# SmartEVSEv2.net
KiCad netlist of a schematic drawn in EAGLE
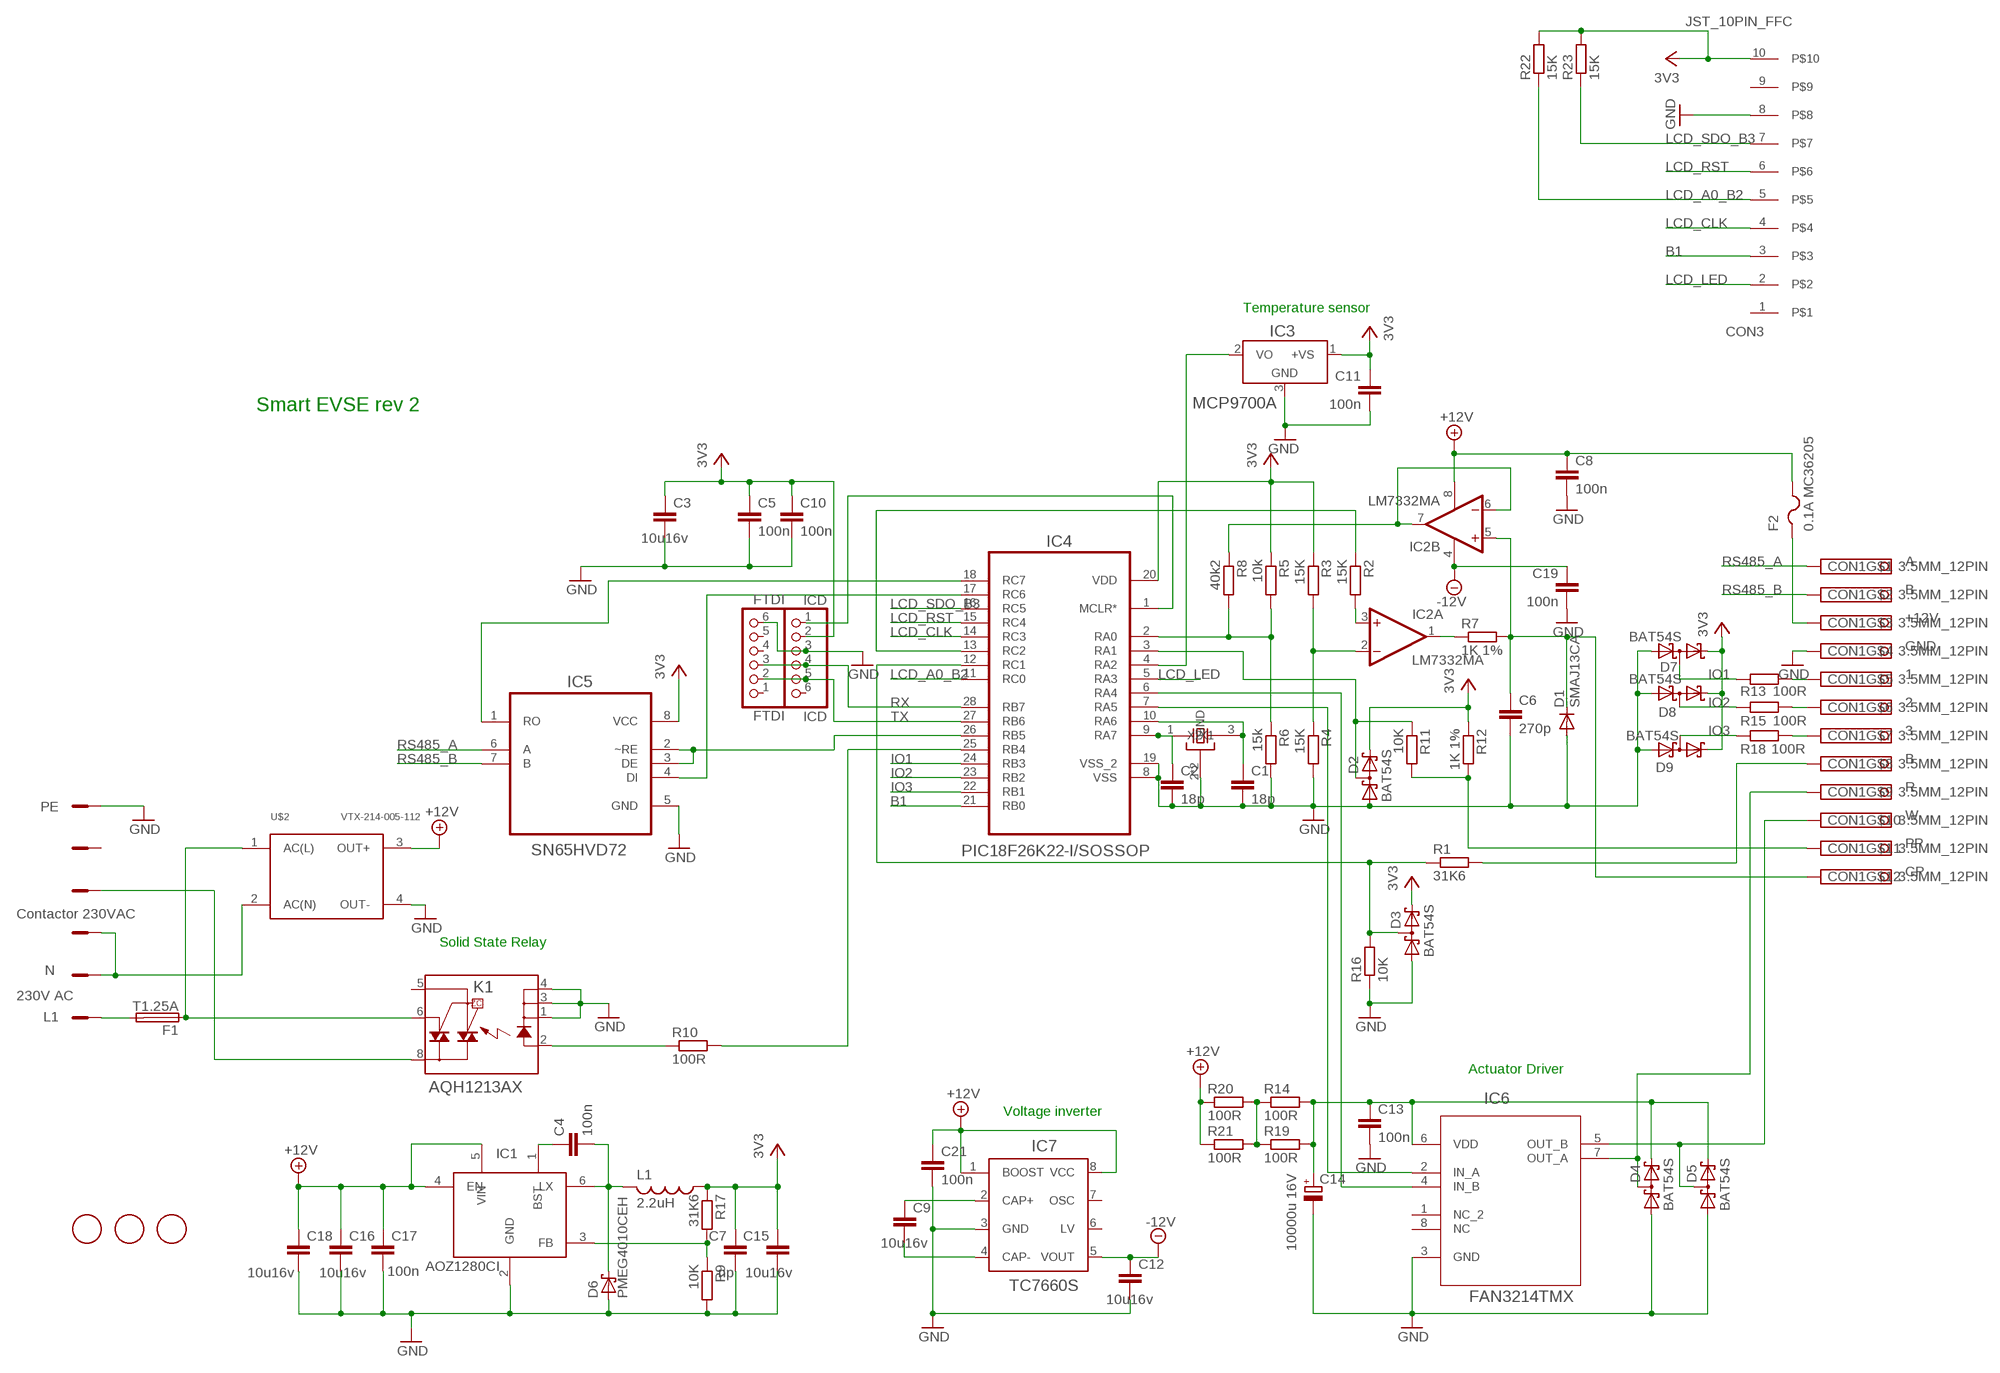
[diagram p0: schematic, sheet 1]

(export (version "E")
  (design (tool "Eeschema 10.0.6"))
  (components
    (comp (ref "C1")
      (value "18p")
      (footprint "eagle-import:C0805")
      (libsource (lib "eagle-import") (part "C-EUC0805"))
    )
    (comp (ref "C2")
      (value "18p")
      (footprint "eagle-import:C0805")
      (libsource (lib "eagle-import") (part "C-EUC0805"))
    )
    (comp (ref "C3")
      (value "10u16v")
      (footprint "eagle-import:C1206")
      (libsource (lib "eagle-import") (part "C-EUC1206"))
    )
    (comp (ref "C4")
      (value "100n")
      (footprint "eagle-import:C0805")
      (libsource (lib "eagle-import") (part "C-EUC0805"))
    )
    (comp (ref "C5")
      (value "100n")
      (footprint "eagle-import:C0805")
      (libsource (lib "eagle-import") (part "C-EUC0805"))
    )
    (comp (ref "C6")
      (value "270p")
      (footprint "eagle-import:C0805")
      (libsource (lib "eagle-import") (part "C-EUC0805"))
    )
    (comp (ref "C7")
      (value "np")
      (footprint "eagle-import:C1206")
      (libsource (lib "eagle-import") (part "C-EUC1206"))
    )
    (comp (ref "C8")
      (value "100n")
      (footprint "eagle-import:C0805")
      (libsource (lib "eagle-import") (part "C-EUC0805"))
    )
    (comp (ref "C9")
      (value "10u16v")
      (footprint "eagle-import:C1206")
      (libsource (lib "eagle-import") (part "C-EUC1206"))
    )
    (comp (ref "C10")
      (value "100n")
      (footprint "eagle-import:C0805")
      (libsource (lib "eagle-import") (part "C-EUC0805"))
    )
    (comp (ref "C11")
      (value "100n")
      (footprint "eagle-import:C0805")
      (libsource (lib "eagle-import") (part "C-EUC0805"))
    )
    (comp (ref "C12")
      (value "10u16v")
      (footprint "eagle-import:C1206")
      (libsource (lib "eagle-import") (part "C-EUC1206"))
    )
    (comp (ref "C13")
      (value "100n")
      (footprint "eagle-import:C0805")
      (libsource (lib "eagle-import") (part "C-EUC0805"))
    )
    (comp (ref "C14")
      (value "10000u 16V")
      (footprint "eagle-import:EB22,5D")
      (libsource (lib "eagle-import") (part "CPOL-EUE10-22.5"))
    )
    (comp (ref "C15")
      (value "10u16v")
      (footprint "eagle-import:C1206")
      (libsource (lib "eagle-import") (part "C-EUC1206"))
    )
    (comp (ref "C16")
      (value "10u16v")
      (footprint "eagle-import:C1206")
      (libsource (lib "eagle-import") (part "C-EUC1206"))
    )
    (comp (ref "C17")
      (value "100n")
      (footprint "eagle-import:C0805")
      (libsource (lib "eagle-import") (part "C-EUC0805"))
    )
    (comp (ref "C18")
      (value "10u16v")
      (footprint "eagle-import:C1206")
      (libsource (lib "eagle-import") (part "C-EUC1206"))
    )
    (comp (ref "C19")
      (value "100n")
      (footprint "eagle-import:C0805")
      (libsource (lib "eagle-import") (part "C-EUC0805"))
    )
    (comp (ref "C21")
      (value "100n")
      (footprint "eagle-import:C0805")
      (libsource (lib "eagle-import") (part "C-EUC0805"))
    )
    (comp (ref "CON1")
      (value "3.5MM_12PIN")
      (footprint "eagle-import:12PIN")
      (libsource (lib "eagle-import") (part "3.5MM_12PIN"))
    )
    (comp (ref "CON3")
      (value "JST_10PIN_FFC")
      (footprint "eagle-import:JST_10PIN_FFC")
      (libsource (lib "eagle-import") (part "JST_10PIN_FFC"))
    )
    (comp (ref "D1")
      (value "SMAJ13CA")
      (footprint "eagle-import:DO214AC")
      (libsource (lib "eagle-import") (part "DIODE-DO214AC"))
    )
    (comp (ref "D2")
      (value "BAT54S")
      (footprint "eagle-import:SOT23")
      (libsource (lib "eagle-import") (part "BAT54S"))
    )
    (comp (ref "D3")
      (value "BAT54S")
      (footprint "eagle-import:SOT23")
      (libsource (lib "eagle-import") (part "BAT54S"))
    )
    (comp (ref "D4")
      (value "BAT54S")
      (footprint "eagle-import:SOT23")
      (libsource (lib "eagle-import") (part "BAT54S"))
    )
    (comp (ref "D5")
      (value "BAT54S")
      (footprint "eagle-import:SOT23")
      (libsource (lib "eagle-import") (part "BAT54S"))
    )
    (comp (ref "D6")
      (value "PMEG4010CEH")
      (footprint "eagle-import:SOD-123FL")
      (libsource (lib "eagle-import") (part "PMEG4010CEH"))
    )
    (comp (ref "D7")
      (value "BAT54S")
      (footprint "eagle-import:SOT23")
      (libsource (lib "eagle-import") (part "BAT54S"))
    )
    (comp (ref "D8")
      (value "BAT54S")
      (footprint "eagle-import:SOT23")
      (libsource (lib "eagle-import") (part "BAT54S"))
    )
    (comp (ref "D9")
      (value "BAT54S")
      (footprint "eagle-import:SOT23")
      (libsource (lib "eagle-import") (part "BAT54S"))
    )
    (comp (ref "F1")
      (value "T1.25A")
      (footprint "eagle-import:TE5")
      (libsource (lib "eagle-import") (part "FUSETE5"))
    )
    (comp (ref "F2")
      (value "0.1A MC36205")
      (footprint "eagle-import:1812")
      (libsource (lib "eagle-import") (part "PTCFUSE-1812"))
    )
    (comp (ref "FTDI")
      (value "FTDI")
      (footprint "eagle-import:1X06-BIGLOCK")
      (libsource (lib "eagle-import") (part "PINHD-1X6LOCK"))
    )
    (comp (ref "IC1")
      (value "AOZ1280CI")
      (footprint "eagle-import:SOT23-6")
      (libsource (lib "eagle-import") (part "AOZ1280CISOT23"))
    )
    (comp (ref "IC2")
      (value "LM7332MA")
      (footprint "eagle-import:SO08")
      (libsource (lib "eagle-import") (part "1458DLM"))
    )
    (comp (ref "IC3")
      (value "MCP9700A")
      (footprint "eagle-import:SOT23")
      (libsource (lib "eagle-import") (part "LM50"))
    )
    (comp (ref "IC4")
      (value "PIC18F26K22-I/SOSSOP")
      (footprint "eagle-import:SOP65P780X200-28N")
      (libsource (lib "eagle-import") (part "PIC18F25K22-I/SOSSOP"))
    )
    (comp (ref "IC5")
      (value "SN65HVD72")
      (footprint "eagle-import:SOIC127P600X175-8N")
      (fields (field (name "MPN") "MAX487ECSA+"))
      (libsource (lib "eagle-import") (part "MAX487ECSA+"))
    )
    (comp (ref "IC6")
      (value "FAN3214TMX")
      (footprint "eagle-import:SOIC127P600X175-8N")
      (fields (field (name "MPN") "TC4424AVOA"))
      (libsource (lib "eagle-import") (part "TC4424AVOA"))
    )
    (comp (ref "IC7")
      (value "TC7660S")
      (footprint "eagle-import:SO08")
      (libsource (lib "eagle-import") (part "TL7660"))
    )
    (comp (ref "ICD")
      (value "ICD")
      (footprint "eagle-import:1X06")
      (libsource (lib "eagle-import") (part "pinhead_PINHD-1X6"))
    )
    (comp (ref "K1")
      (value "AQH1213AX")
      (footprint "eagle-import:DIL07SMD")
      (libsource (lib "eagle-import") (part "AQH213A"))
    )
    (comp (ref "L1")
      (value "2.2uH")
      (footprint "eagle-import:MCSD43")
      (libsource (lib "eagle-import") (part "MCSD43"))
    )
    (comp (ref "Q1")
      (value "CTS_32X25_SMD")
      (footprint "eagle-import:CTS_32X25")
      (libsource (lib "eagle-import") (part "CTS_32X25_SMD"))
    )
    (comp (ref "R1")
      (value "31K6")
      (footprint "eagle-import:R0603")
      (libsource (lib "eagle-import") (part "R-EU_R0603"))
    )
    (comp (ref "R2")
      (value "15K")
      (footprint "eagle-import:R0603")
      (libsource (lib "eagle-import") (part "R-EU_R0603"))
    )
    (comp (ref "R3")
      (value "15K")
      (footprint "eagle-import:R0603")
      (libsource (lib "eagle-import") (part "R-EU_R0603"))
    )
    (comp (ref "R4")
      (value "15K")
      (footprint "eagle-import:R0603")
      (libsource (lib "eagle-import") (part "R-EU_R0603"))
    )
    (comp (ref "R5")
      (value "10k")
      (footprint "eagle-import:R0603")
      (libsource (lib "eagle-import") (part "R-EU_R0603"))
    )
    (comp (ref "R6")
      (value "15k")
      (footprint "eagle-import:R0603")
      (libsource (lib "eagle-import") (part "R-EU_R0603"))
    )
    (comp (ref "R7")
      (value "1K 1%")
      (footprint "eagle-import:R0603")
      (libsource (lib "eagle-import") (part "R-EU_R0603"))
    )
    (comp (ref "R8")
      (value "40k2")
      (footprint "eagle-import:R0603")
      (libsource (lib "eagle-import") (part "R-EU_R0603"))
    )
    (comp (ref "R9")
      (value "10K")
      (footprint "eagle-import:R0603")
      (libsource (lib "eagle-import") (part "R-EU_R0603"))
    )
    (comp (ref "R10")
      (value "100R")
      (footprint "eagle-import:R0603")
      (libsource (lib "eagle-import") (part "R-EU_R0603"))
    )
    (comp (ref "R11")
      (value "10K")
      (footprint "eagle-import:R0603")
      (libsource (lib "eagle-import") (part "R-EU_R0603"))
    )
    (comp (ref "R12")
      (value "1K 1%")
      (footprint "eagle-import:R0603")
      (libsource (lib "eagle-import") (part "R-EU_R0603"))
    )
    (comp (ref "R13")
      (value "100R")
      (footprint "eagle-import:R0603")
      (libsource (lib "eagle-import") (part "R-EU_R0603"))
    )
    (comp (ref "R14")
      (value "100R")
      (footprint "eagle-import:R0603")
      (libsource (lib "eagle-import") (part "R-EU_R0603"))
    )
    (comp (ref "R15")
      (value "100R")
      (footprint "eagle-import:R0603")
      (libsource (lib "eagle-import") (part "R-EU_R0603"))
    )
    (comp (ref "R16")
      (value "10K")
      (footprint "eagle-import:R0603")
      (libsource (lib "eagle-import") (part "R-EU_R0603"))
    )
    (comp (ref "R17")
      (value "31K6")
      (footprint "eagle-import:R0603")
      (libsource (lib "eagle-import") (part "R-EU_R0603"))
    )
    (comp (ref "R18")
      (value "100R")
      (footprint "eagle-import:R0603")
      (libsource (lib "eagle-import") (part "R-EU_R0603"))
    )
    (comp (ref "R19")
      (value "100R")
      (footprint "eagle-import:R0603")
      (libsource (lib "eagle-import") (part "R-EU_R0603"))
    )
    (comp (ref "R20")
      (value "100R")
      (footprint "eagle-import:R0603")
      (libsource (lib "eagle-import") (part "R-EU_R0603"))
    )
    (comp (ref "R21")
      (value "100R")
      (footprint "eagle-import:R0603")
      (libsource (lib "eagle-import") (part "R-EU_R0603"))
    )
    (comp (ref "R22")
      (value "15K")
      (footprint "eagle-import:R0603")
      (libsource (lib "eagle-import") (part "R-EU_R0603"))
    )
    (comp (ref "R23")
      (value "15K")
      (footprint "eagle-import:R0603")
      (libsource (lib "eagle-import") (part "R-EU_R0603"))
    )
    (comp (ref "U$1")
      (value "FIDUCIAL")
      (footprint "eagle-import:FIDUCIAL_1MM")
      (libsource (lib "eagle-import") (part "FIDUCIAL"))
    )
    (comp (ref "U$2")
      (value "VTX-214-005-112")
      (footprint "eagle-import:VTX-214-005-112")
      (libsource (lib "eagle-import") (part "VTX-214-005-112"))
    )
    (comp (ref "U$3")
      (value "FIDUCIAL")
      (footprint "eagle-import:FIDUCIAL_1MM")
      (libsource (lib "eagle-import") (part "FIDUCIAL"))
    )
    (comp (ref "U$4")
      (value "FIDUCIAL")
      (footprint "eagle-import:FIDUCIAL_1MM")
      (libsource (lib "eagle-import") (part "FIDUCIAL"))
    )
    (comp (ref "X2")
      (value "AST027-06")
      (footprint "eagle-import:P_AST027-06")
      (libsource (lib "eagle-import") (part "AST027-06"))
    )
  )
  (nets
    (net (code "1") (name "+12V") (class "Default")
      (node (ref "C16") (pin "1") (pinfunction "1_1") (pintype "passive"))
      (node (ref "C17") (pin "1") (pinfunction "1_1") (pintype "passive"))
      (node (ref "C18") (pin "1") (pinfunction "1_1") (pintype "passive"))
      (node (ref "C21") (pin "1") (pinfunction "1_1") (pintype "passive"))
      (node (ref "C8") (pin "1") (pinfunction "1_1") (pintype "passive"))
      (node (ref "F2") (pin "2") (pinfunction "2_2") (pintype "passive"))
      (node (ref "IC1") (pin "4") (pinfunction "EN_4") (pintype "bidirectional"))
      (node (ref "IC1") (pin "5") (pinfunction "VIN_5") (pintype "bidirectional"))
      (node (ref "IC2") (pin "8") (pinfunction "V+_8") (pintype "power_in"))
      (node (ref "IC7") (pin "1") (pinfunction "BOOST_1") (pintype "bidirectional"))
      (node (ref "IC7") (pin "8") (pinfunction "VCC_8") (pintype "power_in"))
      (node (ref "R20") (pin "1") (pinfunction "1_1") (pintype "passive"))
      (node (ref "R21") (pin "1") (pinfunction "1_1") (pintype "passive"))
      (node (ref "U$2") (pin "3") (pinfunction "OUT+_3") (pintype "passive"))
    )
    (net (code "2") (name "-12V") (class "Default")
      (node (ref "C12") (pin "1") (pinfunction "1_1") (pintype "passive"))
      (node (ref "C19") (pin "1") (pinfunction "1_1") (pintype "passive"))
      (node (ref "IC2") (pin "4") (pinfunction "V-_4") (pintype "power_in"))
      (node (ref "IC7") (pin "5") (pinfunction "VOUT_5") (pintype "passive"))
    )
    (net (code "3") (name "/B1") (class "Default")
      (node (ref "CON3") (pin "3") (pinfunction "P$3_3") (pintype "bidirectional"))
      (node (ref "IC4") (pin "21") (pinfunction "RB0_21") (pintype "bidirectional"))
    )
    (net (code "4") (name "/IO1") (class "Default")
      (node (ref "D7") (pin "3") (pinfunction "C1A2_3") (pintype "passive"))
      (node (ref "IC4") (pin "24") (pinfunction "RB3_24") (pintype "bidirectional"))
      (node (ref "R13") (pin "1") (pinfunction "1_1") (pintype "passive"))
    )
    (net (code "5") (name "/IO2") (class "Default")
      (node (ref "D8") (pin "3") (pinfunction "C1A2_3") (pintype "passive"))
      (node (ref "IC4") (pin "23") (pinfunction "RB2_23") (pintype "bidirectional"))
      (node (ref "R15") (pin "1") (pinfunction "1_1") (pintype "passive"))
    )
    (net (code "6") (name "/IO3") (class "Default")
      (node (ref "D9") (pin "3") (pinfunction "C1A2_3") (pintype "passive"))
      (node (ref "IC4") (pin "22") (pinfunction "RB1_22") (pintype "bidirectional"))
      (node (ref "R18") (pin "1") (pinfunction "1_1") (pintype "passive"))
    )
    (net (code "7") (name "/LCD_A0_B2") (class "Default")
      (node (ref "CON3") (pin "5") (pinfunction "P$5_5") (pintype "bidirectional"))
      (node (ref "IC4") (pin "11") (pinfunction "RC0_11") (pintype "bidirectional"))
      (node (ref "R22") (pin "1") (pinfunction "1_1") (pintype "passive"))
    )
    (net (code "8") (name "/LCD_CLK") (class "Default")
      (node (ref "CON3") (pin "4") (pinfunction "P$4_4") (pintype "bidirectional"))
      (node (ref "IC4") (pin "14") (pinfunction "RC3_14") (pintype "bidirectional"))
    )
    (net (code "9") (name "/LCD_LED") (class "Default")
      (node (ref "CON3") (pin "2") (pinfunction "P$2_2") (pintype "bidirectional"))
      (node (ref "IC4") (pin "5") (pinfunction "RA3_5") (pintype "bidirectional"))
    )
    (net (code "10") (name "/LCD_RST") (class "Default")
      (node (ref "CON3") (pin "6") (pinfunction "P$6_6") (pintype "bidirectional"))
      (node (ref "IC4") (pin "15") (pinfunction "RC4_15") (pintype "bidirectional"))
    )
    (net (code "11") (name "/LCD_SDO_B3") (class "Default")
      (node (ref "CON3") (pin "7") (pinfunction "P$7_7") (pintype "bidirectional"))
      (node (ref "IC4") (pin "16") (pinfunction "RC5_16") (pintype "bidirectional"))
      (node (ref "R23") (pin "1") (pinfunction "1_1") (pintype "passive"))
    )
    (net (code "12") (name "/RS485_A") (class "Default")
      (node (ref "CON1") (pin "1") (pinfunction "K_1") (pintype "passive"))
      (node (ref "IC5") (pin "6") (pinfunction "A_6") (pintype "bidirectional"))
    )
    (net (code "13") (name "/RS485_B") (class "Default")
      (node (ref "CON1") (pin "2") (pinfunction "K_2") (pintype "passive"))
      (node (ref "IC5") (pin "7") (pinfunction "B_7") (pintype "bidirectional"))
    )
    (net (code "14") (name "/RX") (class "Default")
      (node (ref "FTDI") (pin "3") (pinfunction "3_3") (pintype "passive"))
      (node (ref "IC4") (pin "28") (pinfunction "RB7_28") (pintype "bidirectional"))
      (node (ref "ICD") (pin "4") (pinfunction "4_4") (pintype "passive"))
    )
    (net (code "15") (name "/TX") (class "Default")
      (node (ref "FTDI") (pin "2") (pinfunction "2_2") (pintype "passive"))
      (node (ref "IC4") (pin "27") (pinfunction "RB6_27") (pintype "bidirectional"))
      (node (ref "ICD") (pin "5") (pinfunction "5_5") (pintype "passive"))
    )
    (net (code "16") (name "3V3") (class "Default")
      (node (ref "C10") (pin "1") (pinfunction "1_1") (pintype "passive"))
      (node (ref "C11") (pin "1") (pinfunction "1_1") (pintype "passive"))
      (node (ref "C15") (pin "2") (pinfunction "2_2") (pintype "passive"))
      (node (ref "C3") (pin "1") (pinfunction "1_1") (pintype "passive"))
      (node (ref "C5") (pin "1") (pinfunction "1_1") (pintype "passive"))
      (node (ref "C7") (pin "2") (pinfunction "2_2") (pintype "passive"))
      (node (ref "CON3") (pin "10") (pinfunction "P$10_10") (pintype "bidirectional"))
      (node (ref "D2") (pin "2") (pinfunction "C2_2") (pintype "passive"))
      (node (ref "D3") (pin "2") (pinfunction "C2_2") (pintype "passive"))
      (node (ref "D7") (pin "2") (pinfunction "C2_2") (pintype "passive"))
      (node (ref "D8") (pin "2") (pinfunction "C2_2") (pintype "passive"))
      (node (ref "D9") (pin "2") (pinfunction "C2_2") (pintype "passive"))
      (node (ref "IC3") (pin "1") (pinfunction "+VS_1") (pintype "input"))
      (node (ref "IC4") (pin "20") (pinfunction "VDD_20") (pintype "power_in"))
      (node (ref "IC5") (pin "8") (pinfunction "VCC_8") (pintype "power_in"))
      (node (ref "ICD") (pin "2") (pinfunction "2_2") (pintype "passive"))
      (node (ref "L1") (pin "1") (pinfunction "1_1") (pintype "passive"))
      (node (ref "R12") (pin "1") (pinfunction "1_1") (pintype "passive"))
      (node (ref "R17") (pin "1") (pinfunction "1_1") (pintype "passive"))
      (node (ref "R22") (pin "2") (pinfunction "2_2") (pintype "passive"))
      (node (ref "R23") (pin "2") (pinfunction "2_2") (pintype "passive"))
      (node (ref "R3") (pin "1") (pinfunction "1_1") (pintype "passive"))
      (node (ref "R5") (pin "1") (pinfunction "1_1") (pintype "passive"))
    )
    (net (code "17") (name "GND") (class "Default")
      (node (ref "C1") (pin "2") (pinfunction "2_2") (pintype "passive"))
      (node (ref "C10") (pin "2") (pinfunction "2_2") (pintype "passive"))
      (node (ref "C11") (pin "2") (pinfunction "2_2") (pintype "passive"))
      (node (ref "C12") (pin "2") (pinfunction "2_2") (pintype "passive"))
      (node (ref "C13") (pin "2") (pinfunction "2_2") (pintype "passive"))
      (node (ref "C14") (pin "-") (pinfunction "-_-") (pintype "passive"))
      (node (ref "C15") (pin "1") (pinfunction "1_1") (pintype "passive"))
      (node (ref "C16") (pin "2") (pinfunction "2_2") (pintype "passive"))
      (node (ref "C17") (pin "2") (pinfunction "2_2") (pintype "passive"))
      (node (ref "C18") (pin "2") (pinfunction "2_2") (pintype "passive"))
      (node (ref "C19") (pin "2") (pinfunction "2_2") (pintype "passive"))
      (node (ref "C2") (pin "2") (pinfunction "2_2") (pintype "passive"))
      (node (ref "C21") (pin "2") (pinfunction "2_2") (pintype "passive"))
      (node (ref "C3") (pin "2") (pinfunction "2_2") (pintype "passive"))
      (node (ref "C5") (pin "2") (pinfunction "2_2") (pintype "passive"))
      (node (ref "C6") (pin "2") (pinfunction "2_2") (pintype "passive"))
      (node (ref "C7") (pin "1") (pinfunction "1_1") (pintype "passive"))
      (node (ref "C8") (pin "2") (pinfunction "2_2") (pintype "passive"))
      (node (ref "CON1") (pin "4") (pinfunction "K_4") (pintype "passive"))
      (node (ref "CON3") (pin "8") (pinfunction "P$8_8") (pintype "bidirectional"))
      (node (ref "D1") (pin "A") (pinfunction "A_A") (pintype "passive"))
      (node (ref "D2") (pin "1") (pinfunction "A1_1") (pintype "passive"))
      (node (ref "D3") (pin "1") (pinfunction "A1_1") (pintype "passive"))
      (node (ref "D4") (pin "1") (pinfunction "A1_1") (pintype "passive"))
      (node (ref "D5") (pin "1") (pinfunction "A1_1") (pintype "passive"))
      (node (ref "D6") (pin "A") (pinfunction "A_A") (pintype "passive"))
      (node (ref "D7") (pin "1") (pinfunction "A1_1") (pintype "passive"))
      (node (ref "D8") (pin "1") (pinfunction "A1_1") (pintype "passive"))
      (node (ref "D9") (pin "1") (pinfunction "A1_1") (pintype "passive"))
      (node (ref "FTDI") (pin "6") (pinfunction "6_6") (pintype "passive"))
      (node (ref "IC1") (pin "2") (pinfunction "GND_2") (pintype "bidirectional"))
      (node (ref "IC3") (pin "3") (pinfunction "GND_3") (pintype "power_in"))
      (node (ref "IC4") (pin "19") (pinfunction "VSS_2_19") (pintype "power_in"))
      (node (ref "IC4") (pin "8") (pinfunction "VSS_8") (pintype "power_in"))
      (node (ref "IC5") (pin "5") (pinfunction "GND_5") (pintype "passive"))
      (node (ref "IC6") (pin "3") (pinfunction "GND_3") (pintype "passive"))
      (node (ref "IC7") (pin "3") (pinfunction "GND_3") (pintype "power_in"))
      (node (ref "ICD") (pin "3") (pinfunction "3_3") (pintype "passive"))
      (node (ref "K1") (pin "1") (pinfunction "K_1") (pintype "passive"))
      (node (ref "K1") (pin "3") (pinfunction "K1_3") (pintype "passive"))
      (node (ref "K1") (pin "4") (pinfunction "K2_4") (pintype "passive"))
      (node (ref "Q1") (pin "2") (pinfunction "GND_2") (pintype "power_in"))
      (node (ref "Q1") (pin "4") (pinfunction "GND_4") (pintype "power_in"))
      (node (ref "R16") (pin "1") (pinfunction "1_1") (pintype "passive"))
      (node (ref "R4") (pin "2") (pinfunction "2_2") (pintype "passive"))
      (node (ref "R6") (pin "2") (pinfunction "2_2") (pintype "passive"))
      (node (ref "R9") (pin "2") (pinfunction "2_2") (pintype "passive"))
      (node (ref "U$2") (pin "4") (pinfunction "OUT-_4") (pintype "passive"))
      (node (ref "X2") (pin "P$6") (pinfunction "SK_P$6") (pintype "passive"))
    )
    (net (code "18") (name "Net-(CON1B-K)") (class "Default")
      (node (ref "CON1") (pin "10") (pinfunction "K_10") (pintype "passive"))
      (node (ref "D5") (pin "3") (pinfunction "C1A2_3") (pintype "passive"))
      (node (ref "IC6") (pin "5") (pinfunction "OUT_B_5") (pintype "output"))
    )
    (net (code "19") (name "Net-(CON1C-K)") (class "Default")
      (node (ref "CON1") (pin "11") (pinfunction "K_11") (pintype "passive"))
      (node (ref "R11") (pin "2") (pinfunction "2_2") (pintype "passive"))
      (node (ref "R12") (pin "2") (pinfunction "2_2") (pintype "passive"))
    )
    (net (code "20") (name "Net-(CON1D-K)") (class "Default")
      (node (ref "C6") (pin "1") (pinfunction "1_1") (pintype "passive"))
      (node (ref "CON1") (pin "12") (pinfunction "K_12") (pintype "passive"))
      (node (ref "D1") (pin "C") (pinfunction "C_C") (pintype "passive"))
      (node (ref "IC2") (pin "5") (pinfunction "+IN_5") (pintype "input"))
      (node (ref "R7") (pin "2") (pinfunction "2_2") (pintype "passive"))
    )
    (net (code "21") (name "Net-(CON1F-K)") (class "Default")
      (node (ref "CON1") (pin "3") (pinfunction "K_3") (pintype "passive"))
      (node (ref "F2") (pin "1") (pinfunction "1_1") (pintype "passive"))
    )
    (net (code "22") (name "Net-(CON1H-K)") (class "Default")
      (node (ref "CON1") (pin "5") (pinfunction "K_5") (pintype "passive"))
      (node (ref "R13") (pin "2") (pinfunction "2_2") (pintype "passive"))
    )
    (net (code "23") (name "Net-(CON1I-K)") (class "Default")
      (node (ref "CON1") (pin "6") (pinfunction "K_6") (pintype "passive"))
      (node (ref "R15") (pin "2") (pinfunction "2_2") (pintype "passive"))
    )
    (net (code "24") (name "Net-(CON1J-K)") (class "Default")
      (node (ref "CON1") (pin "7") (pinfunction "K_7") (pintype "passive"))
      (node (ref "R18") (pin "2") (pinfunction "2_2") (pintype "passive"))
    )
    (net (code "25") (name "Net-(CON1K-K)") (class "Default")
      (node (ref "CON1") (pin "8") (pinfunction "K_8") (pintype "passive"))
      (node (ref "R1") (pin "2") (pinfunction "2_2") (pintype "passive"))
    )
    (net (code "26") (name "Net-(CON1L-K)") (class "Default")
      (node (ref "CON1") (pin "9") (pinfunction "K_9") (pintype "passive"))
      (node (ref "D4") (pin "3") (pinfunction "C1A2_3") (pintype "passive"))
      (node (ref "IC6") (pin "7") (pinfunction "OUT_A_7") (pintype "output"))
    )
    (net (code "27") (name "Net-(D2-C1A2)") (class "Default")
      (node (ref "D2") (pin "3") (pinfunction "C1A2_3") (pintype "passive"))
      (node (ref "IC4") (pin "3") (pinfunction "RA1_3") (pintype "bidirectional"))
      (node (ref "R11") (pin "1") (pinfunction "1_1") (pintype "passive"))
    )
    (net (code "28") (name "Net-(D3-C1A2)") (class "Default")
      (node (ref "D3") (pin "3") (pinfunction "C1A2_3") (pintype "passive"))
      (node (ref "IC4") (pin "12") (pinfunction "RC1_12") (pintype "bidirectional"))
      (node (ref "R1") (pin "1") (pinfunction "1_1") (pintype "passive"))
      (node (ref "R16") (pin "2") (pinfunction "2_2") (pintype "passive"))
    )
    (net (code "29") (name "Net-(D4-C2)") (class "Default")
      (node (ref "C13") (pin "1") (pinfunction "1_1") (pintype "passive"))
      (node (ref "C14") (pin "+") (pinfunction "+_+") (pintype "passive"))
      (node (ref "D4") (pin "2") (pinfunction "C2_2") (pintype "passive"))
      (node (ref "D5") (pin "2") (pinfunction "C2_2") (pintype "passive"))
      (node (ref "IC6") (pin "6") (pinfunction "VDD_6") (pintype "power_in"))
      (node (ref "R14") (pin "2") (pinfunction "2_2") (pintype "passive"))
      (node (ref "R19") (pin "2") (pinfunction "2_2") (pintype "passive"))
    )
    (net (code "30") (name "Net-(IC1-BST)") (class "Default")
      (node (ref "C4") (pin "1") (pinfunction "1_1") (pintype "passive"))
      (node (ref "IC1") (pin "1") (pinfunction "BST_1") (pintype "bidirectional"))
    )
    (net (code "31") (name "Net-(IC1-FB)") (class "Default")
      (node (ref "IC1") (pin "3") (pinfunction "FB_3") (pintype "bidirectional"))
      (node (ref "R17") (pin "2") (pinfunction "2_2") (pintype "passive"))
      (node (ref "R9") (pin "1") (pinfunction "1_1") (pintype "passive"))
    )
    (net (code "32") (name "Net-(IC1-LX)") (class "Default")
      (node (ref "C4") (pin "2") (pinfunction "2_2") (pintype "passive"))
      (node (ref "D6") (pin "C") (pinfunction "C_C") (pintype "passive"))
      (node (ref "IC1") (pin "6") (pinfunction "LX_6") (pintype "bidirectional"))
      (node (ref "L1") (pin "2") (pinfunction "2_2") (pintype "passive"))
    )
    (net (code "33") (name "Net-(IC2A-+IN)") (class "Default")
      (node (ref "IC2") (pin "3") (pinfunction "+IN_3") (pintype "input"))
      (node (ref "R2") (pin "2") (pinfunction "2_2") (pintype "passive"))
    )
    (net (code "34") (name "Net-(IC2A--IN)") (class "Default")
      (node (ref "IC2") (pin "2") (pinfunction "-IN_2") (pintype "input"))
      (node (ref "R3") (pin "2") (pinfunction "2_2") (pintype "passive"))
      (node (ref "R4") (pin "1") (pinfunction "1_1") (pintype "passive"))
    )
    (net (code "35") (name "Net-(IC2A-OUT)") (class "Default")
      (node (ref "IC2") (pin "1") (pinfunction "OUT_1") (pintype "output"))
      (node (ref "R7") (pin "1") (pinfunction "1_1") (pintype "passive"))
    )
    (net (code "36") (name "Net-(IC2B--IN)") (class "Default")
      (node (ref "IC2") (pin "6") (pinfunction "-IN_6") (pintype "input"))
      (node (ref "IC2") (pin "7") (pinfunction "OUT_7") (pintype "output"))
      (node (ref "R8") (pin "1") (pinfunction "1_1") (pintype "passive"))
    )
    (net (code "37") (name "Net-(IC3-VO)") (class "Default")
      (node (ref "IC3") (pin "2") (pinfunction "VO_2") (pintype "input"))
      (node (ref "IC4") (pin "4") (pinfunction "RA2_4") (pintype "bidirectional"))
    )
    (net (code "38") (name "Net-(IC4-MCLR*)") (class "Default")
      (node (ref "IC4") (pin "1") (pinfunction "MCLR*_1") (pintype "input"))
      (node (ref "ICD") (pin "1") (pinfunction "1_1") (pintype "passive"))
    )
    (net (code "39") (name "Net-(IC4-RA0)") (class "Default")
      (node (ref "IC4") (pin "2") (pinfunction "RA0_2") (pintype "bidirectional"))
      (node (ref "R5") (pin "2") (pinfunction "2_2") (pintype "passive"))
      (node (ref "R6") (pin "1") (pinfunction "1_1") (pintype "passive"))
      (node (ref "R8") (pin "2") (pinfunction "2_2") (pintype "passive"))
    )
    (net (code "40") (name "Net-(IC4-RA4)") (class "Default")
      (node (ref "IC4") (pin "6") (pinfunction "RA4_6") (pintype "bidirectional"))
      (node (ref "IC6") (pin "4") (pinfunction "IN_B_4") (pintype "input"))
    )
    (net (code "41") (name "Net-(IC4-RA5)") (class "Default")
      (node (ref "IC4") (pin "7") (pinfunction "RA5_7") (pintype "bidirectional"))
      (node (ref "IC6") (pin "2") (pinfunction "IN_A_2") (pintype "input"))
    )
    (net (code "42") (name "Net-(IC4-RA6)") (class "Default")
      (node (ref "C1") (pin "1") (pinfunction "1_1") (pintype "passive"))
      (node (ref "IC4") (pin "10") (pinfunction "RA6_10") (pintype "bidirectional"))
      (node (ref "Q1") (pin "3") (pinfunction "X2_3") (pintype "bidirectional"))
    )
    (net (code "43") (name "Net-(IC4-RA7)") (class "Default")
      (node (ref "C2") (pin "1") (pinfunction "1_1") (pintype "passive"))
      (node (ref "IC4") (pin "9") (pinfunction "RA7_9") (pintype "bidirectional"))
      (node (ref "Q1") (pin "1") (pinfunction "X1_1") (pintype "bidirectional"))
    )
    (net (code "44") (name "Net-(IC4-RB4)") (class "Default")
      (node (ref "IC4") (pin "25") (pinfunction "RB4_25") (pintype "bidirectional"))
      (node (ref "R10") (pin "2") (pinfunction "2_2") (pintype "passive"))
    )
    (net (code "45") (name "Net-(IC4-RB5)") (class "Default")
      (node (ref "IC4") (pin "26") (pinfunction "RB5_26") (pintype "bidirectional"))
      (node (ref "IC5") (pin "2") (pinfunction "~{RE}_2") (pintype "input"))
      (node (ref "IC5") (pin "3") (pinfunction "DE_3") (pintype "input"))
    )
    (net (code "46") (name "Net-(IC4-RC2)") (class "Default")
      (node (ref "IC4") (pin "13") (pinfunction "RC2_13") (pintype "bidirectional"))
      (node (ref "R2") (pin "1") (pinfunction "1_1") (pintype "passive"))
    )
    (net (code "47") (name "Net-(IC4-RC6)") (class "Default")
      (node (ref "IC4") (pin "17") (pinfunction "RC6_17") (pintype "bidirectional"))
      (node (ref "IC5") (pin "4") (pinfunction "DI_4") (pintype "input"))
    )
    (net (code "48") (name "Net-(IC4-RC7)") (class "Default")
      (node (ref "IC4") (pin "18") (pinfunction "RC7_18") (pintype "bidirectional"))
      (node (ref "IC5") (pin "1") (pinfunction "RO_1") (pintype "output"))
    )
    (net (code "49") (name "Net-(IC7-CAP+)") (class "Default")
      (node (ref "C9") (pin "1") (pinfunction "1_1") (pintype "passive"))
      (node (ref "IC7") (pin "2") (pinfunction "CAP+_2") (pintype "passive"))
    )
    (net (code "50") (name "Net-(IC7-CAP-)") (class "Default")
      (node (ref "C9") (pin "2") (pinfunction "2_2") (pintype "passive"))
      (node (ref "IC7") (pin "4") (pinfunction "CAP-_4") (pintype "passive"))
    )
    (net (code "51") (name "Net-(K1-A)") (class "Default")
      (node (ref "K1") (pin "2") (pinfunction "A_2") (pintype "passive"))
      (node (ref "R10") (pin "1") (pinfunction "1_1") (pintype "passive"))
    )
    (net (code "52") (name "Net-(K1-DS1)") (class "Default")
      (node (ref "K1") (pin "8") (pinfunction "DS1_8") (pintype "passive"))
      (node (ref "X2") (pin "P$4") (pinfunction "SK_P$4") (pintype "passive"))
    )
    (net (code "53") (name "Net-(K1-DS3)") (class "Default")
      (node (ref "F1") (pin "1") (pinfunction "1_1") (pintype "passive"))
      (node (ref "K1") (pin "6") (pinfunction "DS3_6") (pintype "passive"))
      (node (ref "U$2") (pin "1") (pinfunction "AC(L)_1") (pintype "input"))
    )
    (net (code "54") (name "Net-(R14-Pad1)") (class "Default")
      (node (ref "R14") (pin "1") (pinfunction "1_1") (pintype "passive"))
      (node (ref "R19") (pin "1") (pinfunction "1_1") (pintype "passive"))
      (node (ref "R20") (pin "2") (pinfunction "2_2") (pintype "passive"))
      (node (ref "R21") (pin "2") (pinfunction "2_2") (pintype "passive"))
    )
    (net (code "55") (name "Net-(U$2-AC(N))") (class "Default")
      (node (ref "U$2") (pin "2") (pinfunction "AC(N)_2") (pintype "input"))
      (node (ref "X2") (pin "P$2") (pinfunction "SK_P$2") (pintype "passive"))
      (node (ref "X2") (pin "P$3") (pinfunction "SK_P$3") (pintype "passive"))
    )
    (net (code "56") (name "Net-(X2A-SK)") (class "Default")
      (node (ref "F1") (pin "2") (pinfunction "2_2") (pintype "passive"))
      (node (ref "X2") (pin "P$1") (pinfunction "SK_P$1") (pintype "passive"))
    )
    (net (code "57") (name "unconnected-(CON3-P$1-Pad1)") (class "Default")
      (node (ref "CON3") (pin "1") (pinfunction "P$1_1") (pintype "bidirectional"))
    )
    (net (code "58") (name "unconnected-(CON3-P$9-Pad9)") (class "Default")
      (node (ref "CON3") (pin "9") (pinfunction "P$9_9") (pintype "bidirectional"))
    )
    (net (code "59") (name "unconnected-(FTDI-Pad1)") (class "Default")
      (node (ref "FTDI") (pin "1") (pinfunction "1_1") (pintype "passive"))
    )
    (net (code "60") (name "unconnected-(FTDI-Pad4)") (class "Default")
      (node (ref "FTDI") (pin "4") (pinfunction "4_4") (pintype "passive"))
    )
    (net (code "61") (name "unconnected-(FTDI-Pad5)") (class "Default")
      (node (ref "FTDI") (pin "5") (pinfunction "5_5") (pintype "passive"))
    )
    (net (code "62") (name "unconnected-(IC6-NC-Pad8)") (class "Default")
      (node (ref "IC6") (pin "8") (pinfunction "NC_8") (pintype "no_connect"))
    )
    (net (code "63") (name "unconnected-(IC6-NC_2-Pad1)") (class "Default")
      (node (ref "IC6") (pin "1") (pinfunction "NC_2_1") (pintype "no_connect"))
    )
    (net (code "64") (name "unconnected-(IC7-LV-Pad6)") (class "Default")
      (node (ref "IC7") (pin "6") (pinfunction "LV_6") (pintype "passive"))
    )
    (net (code "65") (name "unconnected-(IC7-OSC-Pad7)") (class "Default")
      (node (ref "IC7") (pin "7") (pinfunction "OSC_7") (pintype "input"))
    )
    (net (code "66") (name "unconnected-(ICD-Pad6)") (class "Default")
      (node (ref "ICD") (pin "6") (pinfunction "6_6") (pintype "passive"))
    )
    (net (code "67") (name "unconnected-(K1-DS2-Pad5)") (class "Default")
      (node (ref "K1") (pin "5") (pinfunction "DS2_5") (pintype "passive"))
    )
    (net (code "68") (name "unconnected-(X2E-SK-PadP$5)") (class "Default")
      (node (ref "X2") (pin "P$5") (pinfunction "SK_P$5") (pintype "passive"))
    )
  )
)
